# power_board.net
KiCad netlist of a schematic drawn in EAGLE
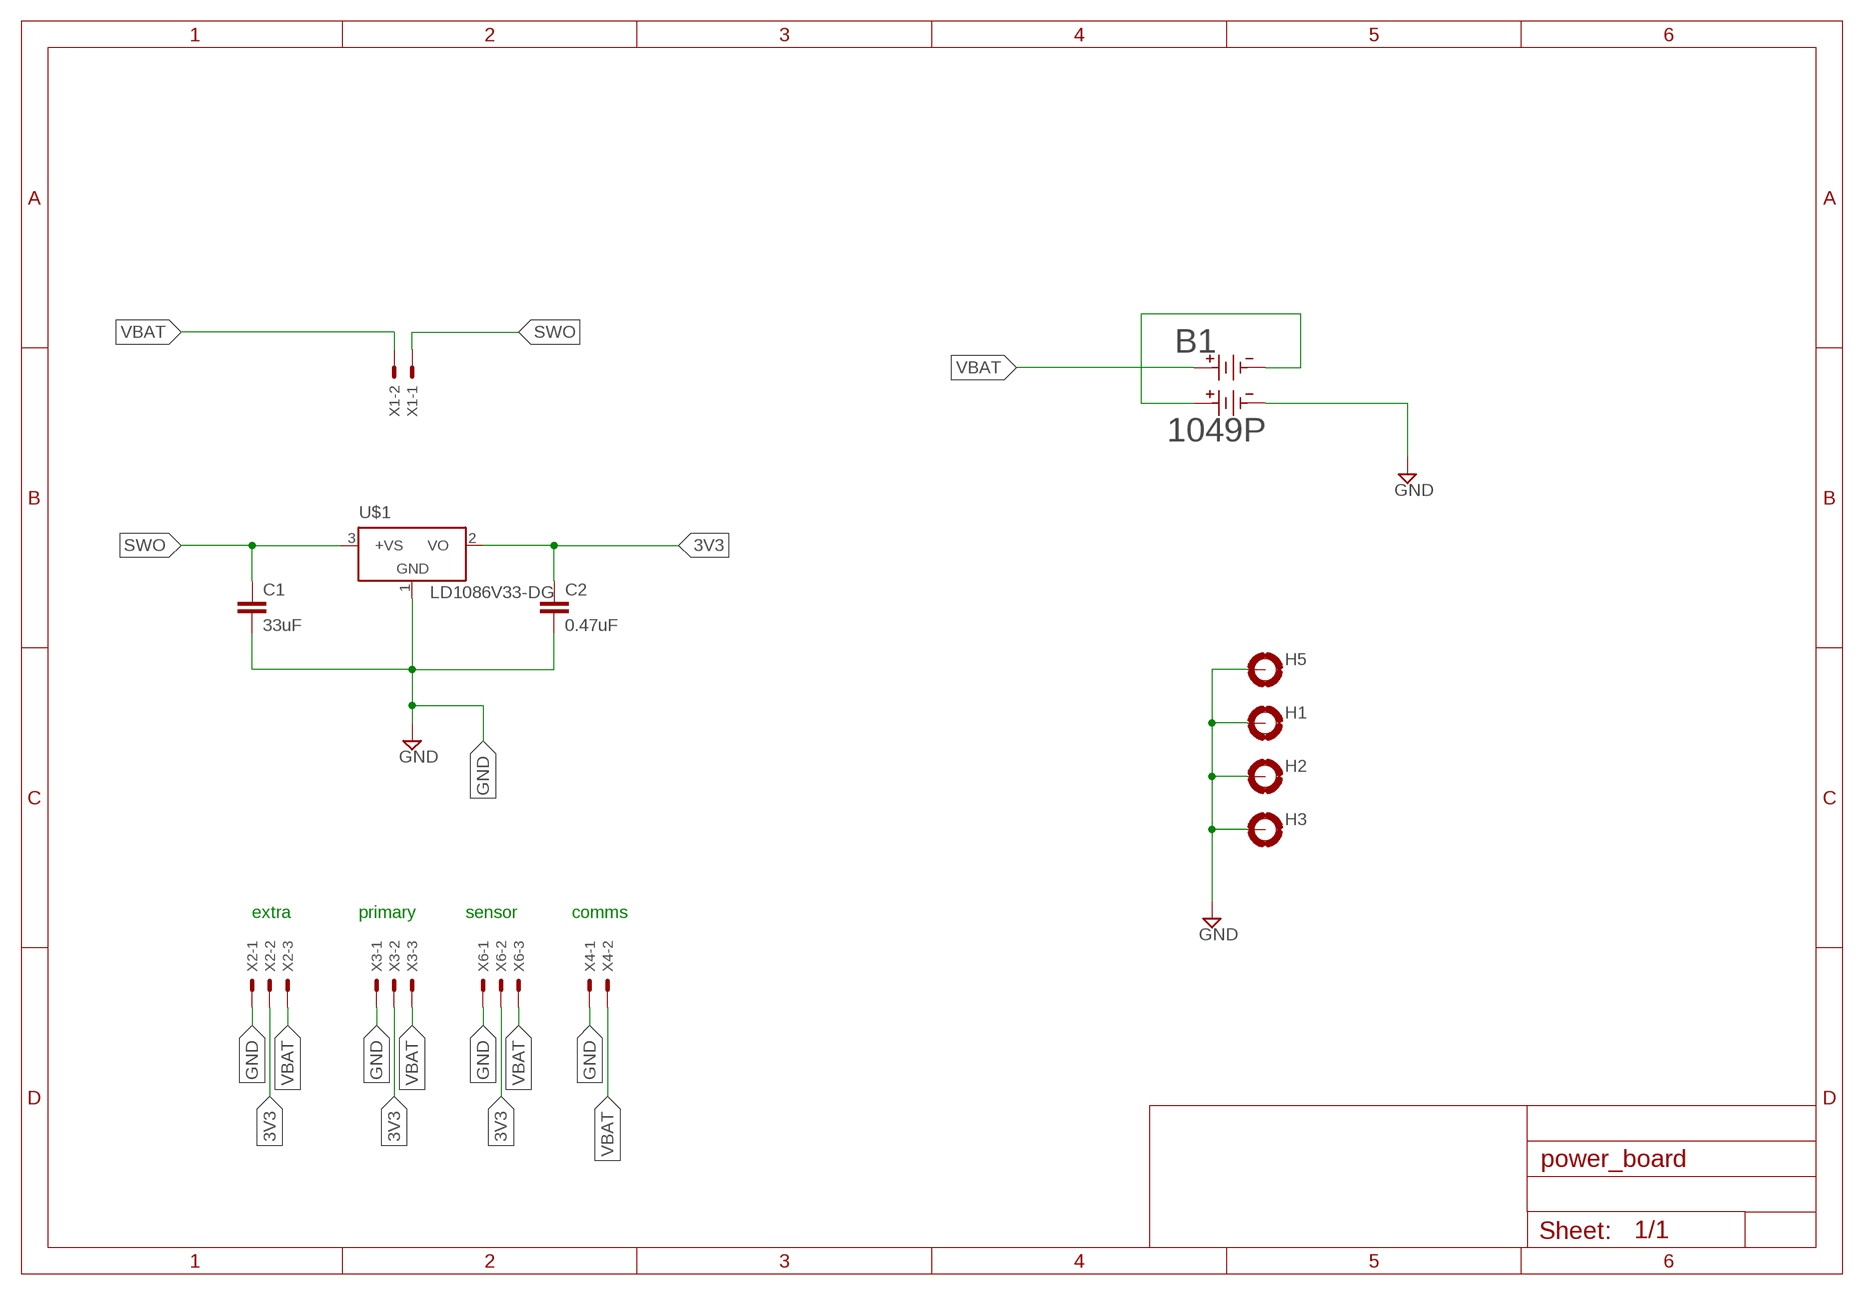
[diagram p0: schematic, sheet 1]

(export (version "E")
  (design (tool "Eeschema 10.0.6"))
  (components
    (comp (ref "B1")
      (value "1049P")
      (footprint "eagle-import:1049P_KEY")
      (fields (field (name "COPYRIGHT") "Copyright (C) 2024 Ultra Librarian. All rights reserved."))
      (libsource (lib "eagle-import") (part "1049P"))
    )
    (comp (ref "C1")
      (value "33uF")
      (footprint "eagle-import:C2.5-3")
      (libsource (lib "eagle-import") (part "C2,5-3"))
    )
    (comp (ref "C2")
      (value "0.47uF")
      (footprint "eagle-import:C2.5-3")
      (libsource (lib "eagle-import") (part "C2,5-3"))
    )
    (comp (ref "H1")
      (value "MOUNT-PAD-ROUND3.0")
      (footprint "eagle-import:3,0-PAD")
      (libsource (lib "eagle-import") (part "MOUNT-PAD-ROUND3.0"))
    )
    (comp (ref "H2")
      (value "MOUNT-PAD-ROUND3.0")
      (footprint "eagle-import:3,0-PAD")
      (libsource (lib "eagle-import") (part "MOUNT-PAD-ROUND3.0"))
    )
    (comp (ref "H3")
      (value "MOUNT-PAD-ROUND3.0")
      (footprint "eagle-import:3,0-PAD")
      (libsource (lib "eagle-import") (part "MOUNT-PAD-ROUND3.0"))
    )
    (comp (ref "H5")
      (value "MOUNT-PAD-ROUND3.0")
      (footprint "eagle-import:3,0-PAD")
      (libsource (lib "eagle-import") (part "MOUNT-PAD-ROUND3.0"))
    )
    (comp (ref "U$1")
      (value "LD1086V33-DG")
      (footprint "eagle-import:TO220H")
      (libsource (lib "eagle-import") (part "LD1086V33-DG"))
    )
    (comp (ref "X1")
      (value "JST-XH-02-PIN")
      (footprint "eagle-import:JST-XH_S2B")
      (libsource (lib "eagle-import") (part "JST-XH-02-PIN"))
    )
    (comp (ref "X2")
      (value "JST-XH-03-PIN")
      (footprint "eagle-import:JST-XH_S3B")
      (libsource (lib "eagle-import") (part "JST-XH-03-PIN"))
    )
    (comp (ref "X3")
      (value "JST-XH-03-PIN")
      (footprint "eagle-import:JST-XH_S3B")
      (libsource (lib "eagle-import") (part "JST-XH-03-PIN"))
    )
    (comp (ref "X4")
      (value "JST-XH-02-PIN")
      (footprint "eagle-import:JST-XH_S2B")
      (libsource (lib "eagle-import") (part "JST-XH-02-PIN"))
    )
    (comp (ref "X6")
      (value "JST-XH-03-PIN")
      (footprint "eagle-import:JST-XH_S3B")
      (libsource (lib "eagle-import") (part "JST-XH-03-PIN"))
    )
  )
  (nets
    (net (code "1") (name "3V3") (class "Default")
      (node (ref "C2") (pin "1") (pinfunction "1_1") (pintype "passive"))
      (node (ref "U$1") (pin "2") (pinfunction "VO_2") (pintype "input"))
      (node (ref "X2") (pin "PIN2") (pinfunction "S_PIN2") (pintype "passive"))
      (node (ref "X3") (pin "PIN2") (pinfunction "S_PIN2") (pintype "passive"))
      (node (ref "X6") (pin "PIN2") (pinfunction "S_PIN2") (pintype "passive"))
    )
    (net (code "2") (name "GND") (class "Default")
      (node (ref "B1") (pin "3") (pinfunction "3_3") (pintype "passive"))
      (node (ref "C1") (pin "2") (pinfunction "2_2") (pintype "passive"))
      (node (ref "C2") (pin "2") (pinfunction "2_2") (pintype "passive"))
      (node (ref "H1") (pin "B3,0") (pinfunction "MOUNT_B3,0") (pintype "passive"))
      (node (ref "H2") (pin "B3,0") (pinfunction "MOUNT_B3,0") (pintype "passive"))
      (node (ref "H3") (pin "B3,0") (pinfunction "MOUNT_B3,0") (pintype "passive"))
      (node (ref "H5") (pin "B3,0") (pinfunction "MOUNT_B3,0") (pintype "passive"))
      (node (ref "U$1") (pin "1") (pinfunction "GND_1") (pintype "power_in"))
      (node (ref "X2") (pin "PIN1") (pinfunction "S_PIN1") (pintype "passive"))
      (node (ref "X3") (pin "PIN1") (pinfunction "S_PIN1") (pintype "passive"))
      (node (ref "X4") (pin "PIN1") (pinfunction "S_PIN1") (pintype "passive"))
      (node (ref "X6") (pin "PIN1") (pinfunction "S_PIN1") (pintype "passive"))
    )
    (net (code "3") (name "Net-(B1-Pad2)") (class "Default")
      (node (ref "B1") (pin "2") (pinfunction "2_2") (pintype "passive"))
      (node (ref "B1") (pin "4") (pinfunction "4_4") (pintype "passive"))
    )
    (net (code "4") (name "SWO") (class "Default")
      (node (ref "C1") (pin "1") (pinfunction "1_1") (pintype "passive"))
      (node (ref "U$1") (pin "3") (pinfunction "+VS_3") (pintype "input"))
      (node (ref "X1") (pin "PIN1") (pinfunction "S_PIN1") (pintype "passive"))
    )
    (net (code "5") (name "VBAT") (class "Default")
      (node (ref "B1") (pin "1") (pinfunction "1_1") (pintype "passive"))
      (node (ref "X1") (pin "PIN2") (pinfunction "S_PIN2") (pintype "passive"))
      (node (ref "X2") (pin "PIN3") (pinfunction "S_PIN3") (pintype "passive"))
      (node (ref "X3") (pin "PIN3") (pinfunction "S_PIN3") (pintype "passive"))
      (node (ref "X4") (pin "PIN2") (pinfunction "S_PIN2") (pintype "passive"))
      (node (ref "X6") (pin "PIN3") (pinfunction "S_PIN3") (pintype "passive"))
    )
  )
)
